# 05_dac.net
KiCad netlist of a schematic drawn in Altium Designer
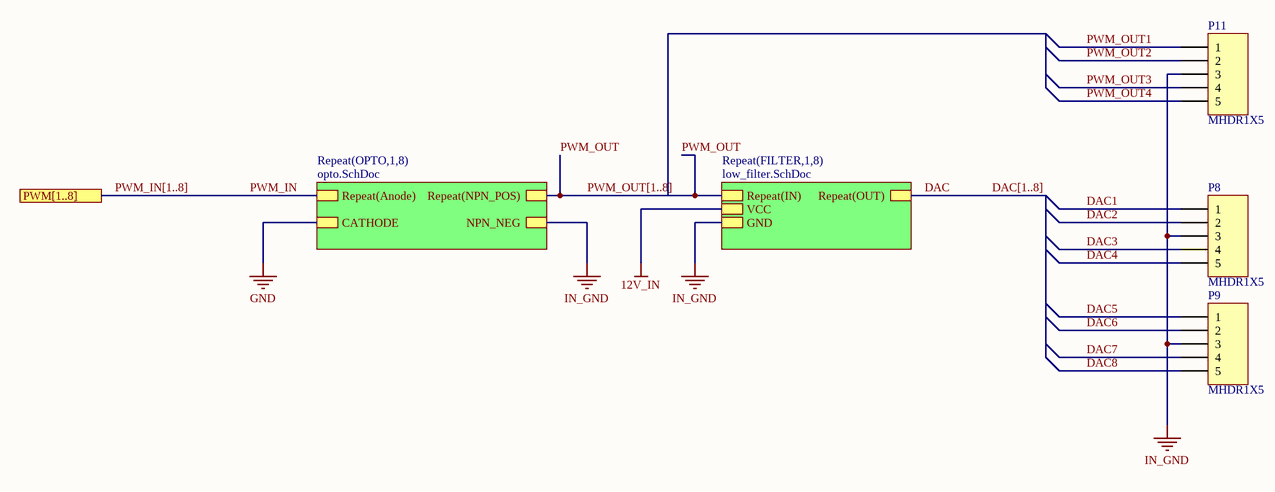
[diagram p0: 05_dac.SchDoc]

(export (version "E")
  (design (tool "Eeschema 10.0.6"))
  (components
    (comp (ref "P8")
      (value "MHDR1X5")
      (footprint "MHDR1X5")
      (description "Header, 5-Pin")
      (fields (field (name "PUBLISHER") "Altium Limited"))
      (libsource (lib "Miscellaneous Connectors") (part "MHDR1X5"))
    )
    (comp (ref "P9")
      (value "MHDR1X5")
      (footprint "MHDR1X5")
      (description "Header, 5-Pin")
      (fields (field (name "PUBLISHER") "Altium Limited"))
      (libsource (lib "Miscellaneous Connectors") (part "MHDR1X5"))
    )
    (comp (ref "P11")
      (value "MHDR1X5")
      (footprint "MHDR1X5")
      (description "Header, 5-Pin")
      (fields (field (name "PUBLISHER") "Altium Limited"))
      (libsource (lib "Miscellaneous Connectors") (part "MHDR1X5"))
    )
  )
  (nets
    (net (code "10") (name "/DAC1") (class "Default")
      (node (ref "P8") (pin "1") (pinfunction "1_1") (pintype "passive"))
    )
    (net (code "11") (name "/DAC2") (class "Default")
      (node (ref "P8") (pin "2") (pinfunction "2_2") (pintype "passive"))
    )
    (net (code "12") (name "/DAC3") (class "Default")
      (node (ref "P8") (pin "4") (pinfunction "4_4") (pintype "passive"))
    )
    (net (code "13") (name "/DAC4") (class "Default")
      (node (ref "P8") (pin "5") (pinfunction "5_5") (pintype "passive"))
    )
    (net (code "14") (name "/DAC5") (class "Default")
      (node (ref "P9") (pin "1") (pinfunction "1_1") (pintype "passive"))
    )
    (net (code "15") (name "/DAC6") (class "Default")
      (node (ref "P9") (pin "2") (pinfunction "2_2") (pintype "passive"))
    )
    (net (code "16") (name "/DAC7") (class "Default")
      (node (ref "P9") (pin "4") (pinfunction "4_4") (pintype "passive"))
    )
    (net (code "17") (name "/DAC8") (class "Default")
      (node (ref "P9") (pin "5") (pinfunction "5_5") (pintype "passive"))
    )
    (net (code "22") (name "/PWM_OUT1") (class "Default")
      (node (ref "P11") (pin "1") (pinfunction "1_1") (pintype "passive"))
    )
    (net (code "23") (name "/PWM_OUT2") (class "Default")
      (node (ref "P11") (pin "2") (pinfunction "2_2") (pintype "passive"))
    )
    (net (code "24") (name "/PWM_OUT3") (class "Default")
      (node (ref "P11") (pin "4") (pinfunction "4_4") (pintype "passive"))
    )
    (net (code "25") (name "/PWM_OUT4") (class "Default")
      (node (ref "P11") (pin "5") (pinfunction "5_5") (pintype "passive"))
    )
    (net (code "28") (name "IN_GND") (class "Default")
      (node (ref "P11") (pin "3") (pinfunction "3_3") (pintype "passive"))
      (node (ref "P8") (pin "3") (pinfunction "3_3") (pintype "passive"))
      (node (ref "P9") (pin "3") (pinfunction "3_3") (pintype "passive"))
    )
  )
)
